# PM12_CONN.net
KiCad netlist of a schematic drawn in Altium Designer
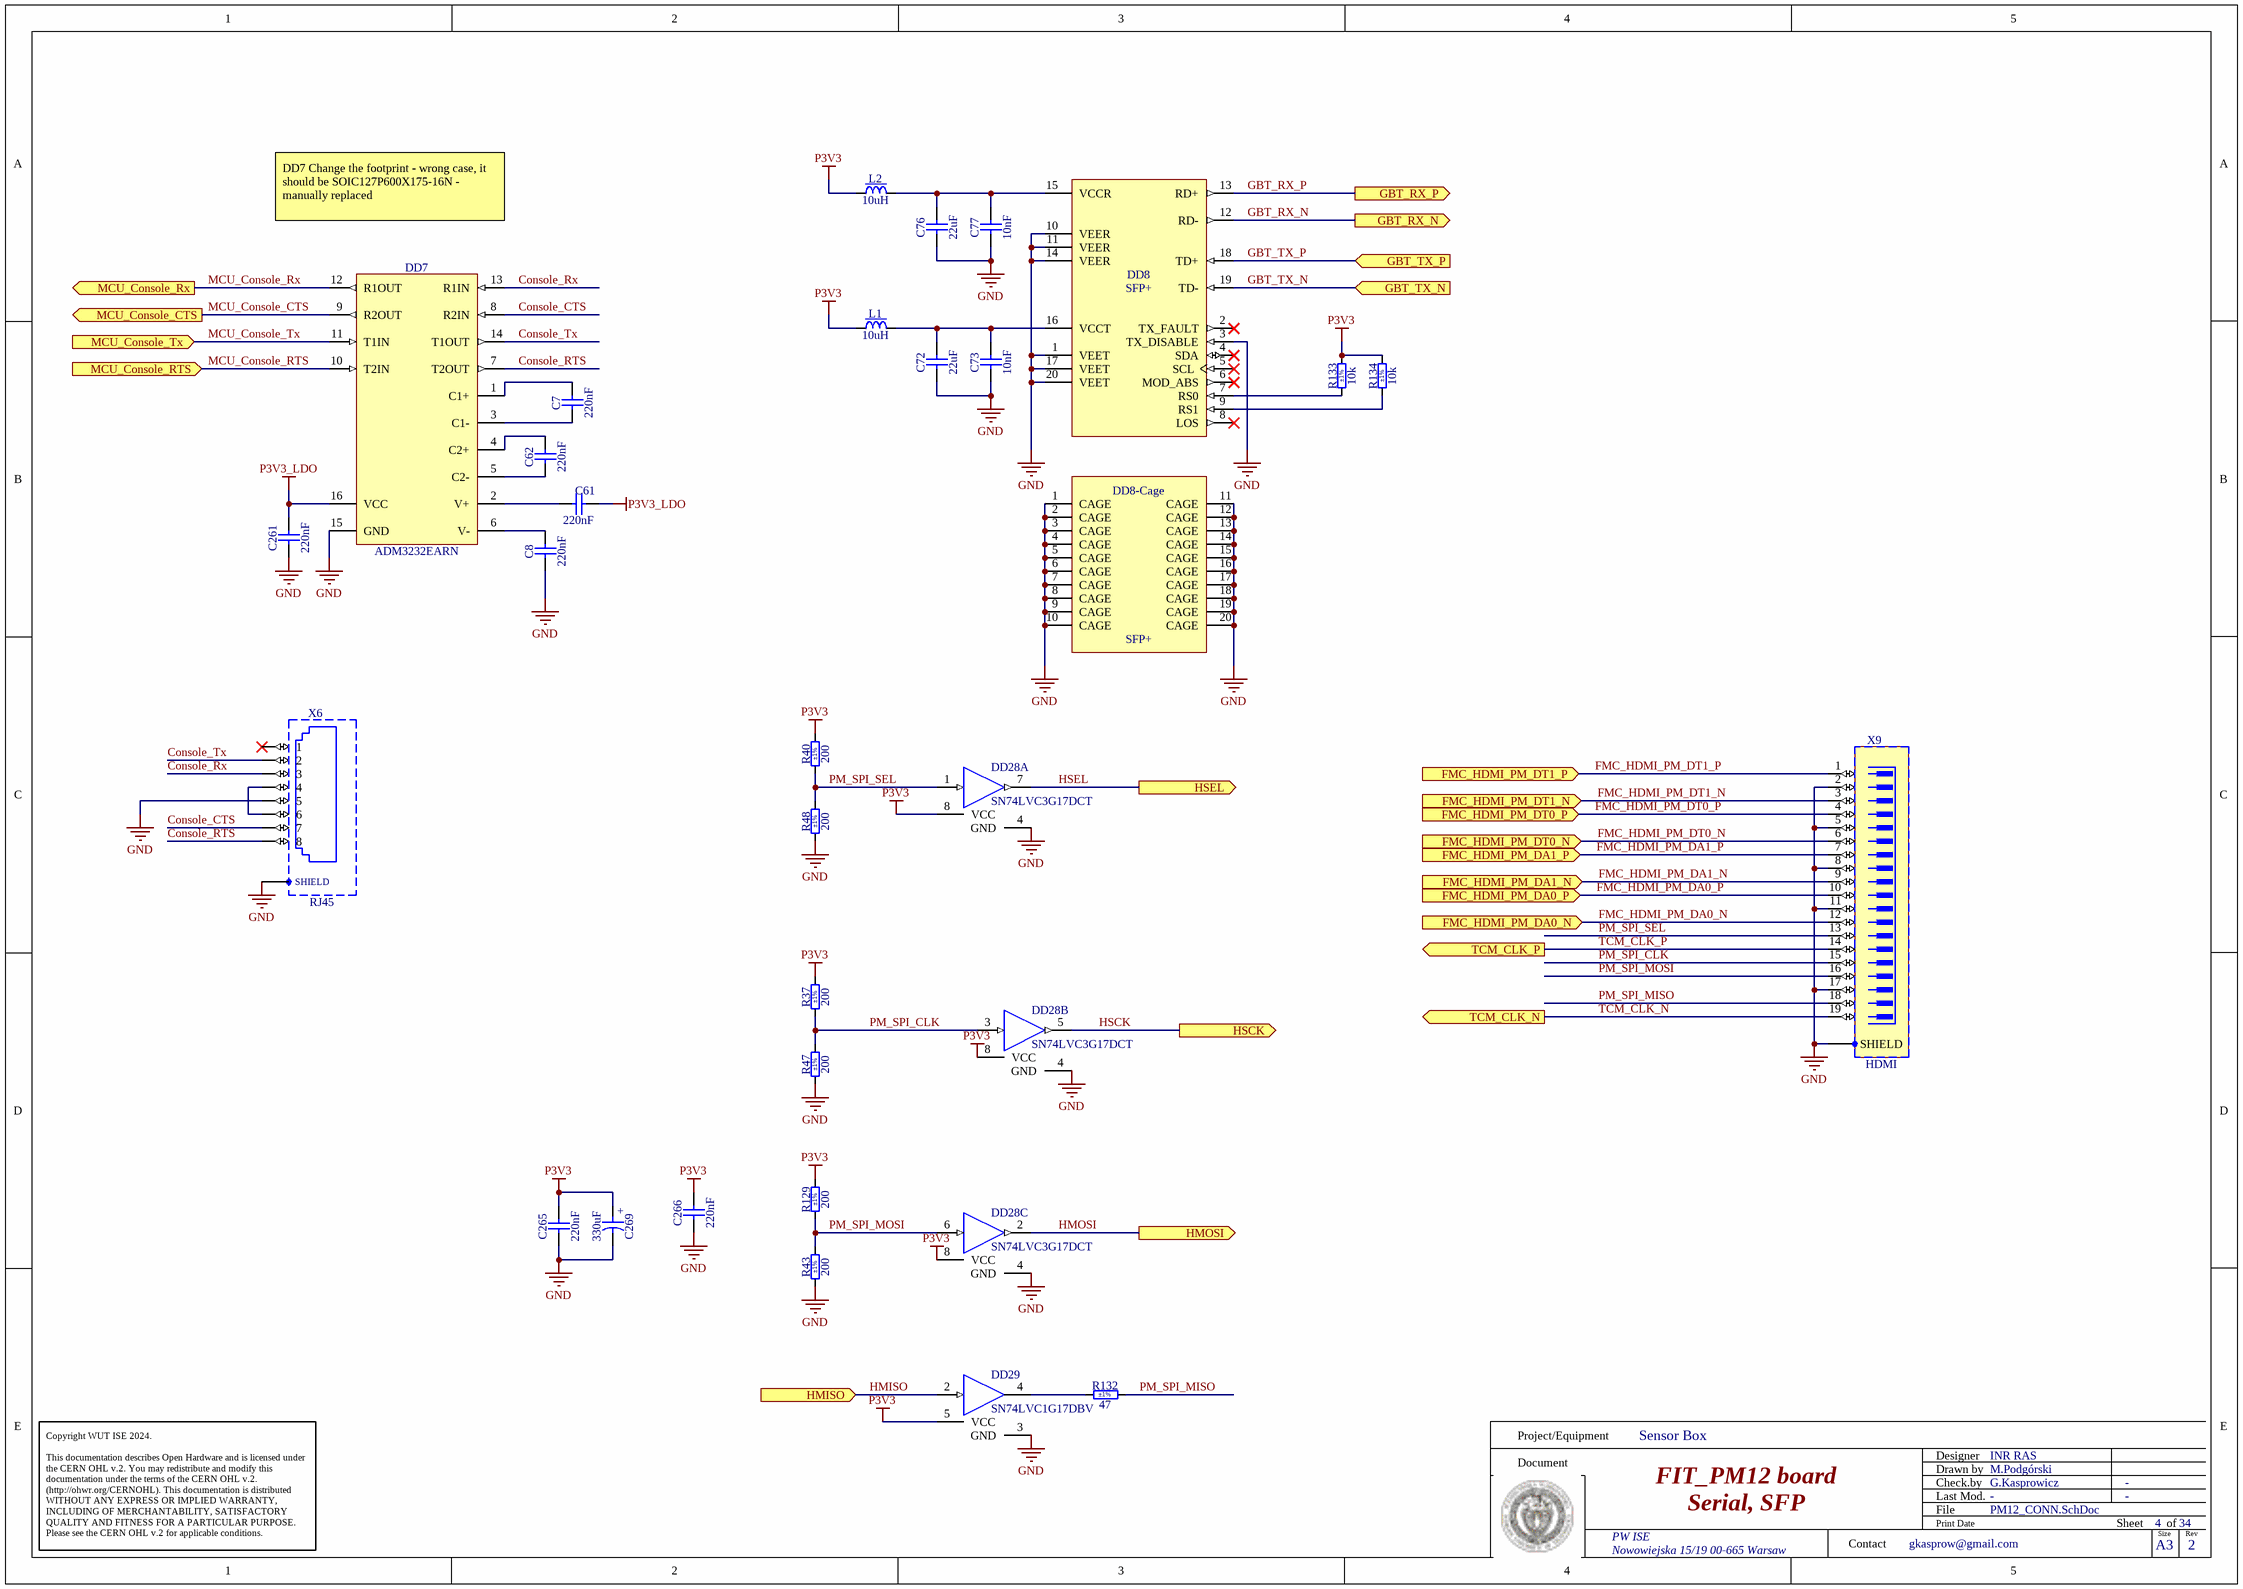
[diagram p0: PM12_CONN.SchDoc]

(export (version "E")
  (design (tool "Eeschema 10.0.6"))
  (components
    (comp (ref "C7")
      (value "220nF")
      (footprint "CAPC2012X135N")
      (description "Non-polarised capacitor")
      (fields
        (field (name "PART NUMBER") "CC0805_220NF_50V_10%_X7R")
        (field (name "VOLTAGE") "50V")
        (field (name "AUTHOR") "CERN DEM JLC")
      )
      (libsource (lib "Capacitors") (part "Capacitor - non polarized"))
    )
    (comp (ref "C8")
      (value "220nF")
      (footprint "CAPC2012X135N")
      (description "Non-polarised capacitor")
      (fields
        (field (name "PART NUMBER") "CC0805_220NF_50V_10%_X7R")
        (field (name "VOLTAGE") "50V")
        (field (name "AUTHOR") "CERN DEM JLC")
      )
      (libsource (lib "Capacitors") (part "Capacitor - non polarized"))
    )
    (comp (ref "C61")
      (value "220nF")
      (footprint "CAPC2012X135N")
      (description "Non-polarised capacitor")
      (fields
        (field (name "PART NUMBER") "CC0805_220NF_50V_10%_X7R")
        (field (name "VOLTAGE") "50V")
        (field (name "AUTHOR") "CERN DEM JLC")
      )
      (libsource (lib "Capacitors") (part "Capacitor - non polarized"))
    )
    (comp (ref "C62")
      (value "220nF")
      (footprint "CAPC2012X135N")
      (description "Non-polarised capacitor")
      (fields
        (field (name "PART NUMBER") "CC0805_220NF_50V_10%_X7R")
        (field (name "VOLTAGE") "50V")
        (field (name "AUTHOR") "CERN DEM JLC")
      )
      (libsource (lib "Capacitors") (part "Capacitor - non polarized"))
    )
    (comp (ref "C72")
      (value "22uF")
      (footprint "CAPC3216X180N")
      (description "Non-polarised capacitor")
      (fields
        (field (name "PART NUMBER") "CC1206_22UF_25V_20%_X5R")
        (field (name "VOLTAGE") "25V")
        (field (name "AUTHOR") "CERN DEM WB")
      )
      (libsource (lib "Capacitors") (part "Capacitor - non polarized"))
    )
    (comp (ref "C73")
      (value "10nF")
      (footprint "CAPC2012X135N")
      (description "Non-polarised capacitor")
      (fields
        (field (name "PART NUMBER") "CC0805_10NF_50V_10%_X7R")
        (field (name "VOLTAGE") "50V")
        (field (name "AUTHOR") "CERN DEM JLC")
      )
      (libsource (lib "Capacitors") (part "Capacitor - non polarized"))
    )
    (comp (ref "C76")
      (value "22uF")
      (footprint "CAPC3216X180N")
      (description "Non-polarised capacitor")
      (fields
        (field (name "PART NUMBER") "CC1206_22UF_25V_20%_X5R")
        (field (name "VOLTAGE") "25V")
        (field (name "AUTHOR") "CERN DEM WB")
      )
      (libsource (lib "Capacitors") (part "Capacitor - non polarized"))
    )
    (comp (ref "C77")
      (value "10nF")
      (footprint "CAPC2012X135N")
      (description "Non-polarised capacitor")
      (fields
        (field (name "PART NUMBER") "CC0805_10NF_50V_10%_X7R")
        (field (name "VOLTAGE") "50V")
        (field (name "AUTHOR") "CERN DEM JLC")
      )
      (libsource (lib "Capacitors") (part "Capacitor - non polarized"))
    )
    (comp (ref "C261")
      (value "220nF")
      (footprint "CAPC2012X135N")
      (description "Non-polarised capacitor")
      (fields
        (field (name "PART NUMBER") "CC0805_220NF_50V_10%_X7R")
        (field (name "VOLTAGE") "50V")
        (field (name "AUTHOR") "CERN DEM JLC")
      )
      (libsource (lib "Capacitors") (part "Capacitor - non polarized"))
    )
    (comp (ref "C265")
      (value "220nF")
      (footprint "CAPC2012X135N")
      (description "Non-polarised capacitor")
      (fields
        (field (name "PART NUMBER") "CC0805_220NF_50V_10%_X7R")
        (field (name "VOLTAGE") "50V")
        (field (name "AUTHOR") "CERN DEM JLC")
      )
      (libsource (lib "Capacitors") (part "Capacitor - non polarized"))
    )
    (comp (ref "C266")
      (value "220nF")
      (footprint "CAPC2012X135N")
      (description "Non-polarised capacitor")
      (fields
        (field (name "PART NUMBER") "CC0805_220NF_50V_10%_X7R")
        (field (name "VOLTAGE") "50V")
        (field (name "AUTHOR") "CERN DEM JLC")
      )
      (libsource (lib "Capacitors") (part "Capacitor - non polarized"))
    )
    (comp (ref "C269")
      (value "330uF")
      (footprint "CAPMP7343X310N")
      (description "Polarised capacitor")
      (fields
        (field (name "PART NUMBER") "CTE7343-31_330UF_6.3V_20%_LESR0015_KEMET_T520")
        (field (name "VOLTAGE") "6.3V")
        (field (name "AUTHOR") "CERN DEM JLC")
      )
      (libsource (lib "Capacitors") (part "Capacitor - polarized"))
    )
    (comp (ref "DD7")
      (value "ADM3232EARN")
      (footprint "SOIC127P600X175-16N")
      (description "±15 kV ESD Protected, 3.3 V, RS-232 Line Driver/Receiver")
      (fields (field (name "MANUFACTURER") "ANALOG DEVICES") (field (name "AUTHOR") "CERN DEM HF"))
      (libsource (lib "ICs And Semiconductors") (part "ADM3232EARN"))
    )
    (comp (ref "DD8")
      (value "SFP+")
      (footprint "AMPHENOL_UE76A203000")
      (description "20 Position SFP+ Connector (Small Form-factor Pluggable)")
      (fields
        (field (name "PART NUMBER") "AMPHENOL_UE76A203000")
        (field (name "MANUFACTURER") "AMPHENOL")
        (field (name "AUTHOR") "CERN DEM BC")
      )
      (libsource (lib "Connectors") (part "SFP+x1"))
    )
    (comp (ref "DD8-Cage")
      (value "SFP+")
      (footprint "AMPHENOL_U77A16131001")
      (description "SFP+ 1x1 Cage (20Pins)")
      (fields
        (field (name "PART NUMBER") "AMPHENOL_U77A16131001")
        (field (name "MANUFACTURER") "AMPHENOL")
        (field (name "AUTHOR") "CERN DEM BC")
      )
      (libsource (lib "Connectors") (part "SFP+ 1x1 Cage (20Pins)"))
    )
    (comp (ref "DD28")
      (value "SN74LVC3G17DCT")
      (footprint "SOP65P400X130-8N")
      (description "Triple Schmitt-Trigger Buffer")
      (fields (field (name "MANUFACTURER") "TEXAS INSTRUMENTS") (field (name "AUTHOR") "CERN DEM HF"))
      (libsource (lib "ICs And Semiconductors") (part "743G17"))
    )
    (comp (ref "DD29")
      (value "SN74LVC1G17DBV")
      (footprint "SOT95P280X145-5N")
      (description "Single Schmitt-Trigger Buffer")
      (fields
        (field (name "PART NUMBER") "SN74LVC1G17DBVR")
        (field (name "MANUFACTURER") "TEXAS INSTRUMENTS")
        (field (name "AUTHOR") "CERN DEM JLC")
      )
      (libsource (lib "ICs And Semiconductors") (part "741G17"))
    )
    (comp (ref "L1")
      (value "10uH")
      (footprint "INDM5552X200N")
      (description "Inductor With Core")
      (fields
        (field (name "PART NUMBER") "IND2020_10UH_20%_VISHAY_IHLP-2020BZ-11")
        (field (name "POWER") "2.2A")
        (field (name "AUTHOR") "CERN DEM HF")
      )
      (libsource (lib "Inductors & Transformers") (part "Inductor With Magnetic core"))
    )
    (comp (ref "L2")
      (value "10uH")
      (footprint "INDM5552X200N")
      (description "Inductor With Core")
      (fields
        (field (name "PART NUMBER") "IND2020_10UH_20%_VISHAY_IHLP-2020BZ-11")
        (field (name "POWER") "2.2A")
        (field (name "AUTHOR") "CERN DEM HF")
      )
      (libsource (lib "Inductors & Transformers") (part "Inductor With Magnetic core"))
    )
    (comp (ref "R37")
      (value "200")
      (footprint "RESC2012X60N")
      (description "Resistor - 1%")
      (fields
        (field (name "TOLERANCE") "±1%")
        (field (name "PART NUMBER") "R0805_200R_1%_0.125W_100PPM")
        (field (name "POWER") "0.125W")
        (field (name "AUTHOR") "CERN DEM JLC")
      )
      (libsource (lib "Resistors") (part "Resistor - 1%"))
    )
    (comp (ref "R40")
      (value "200")
      (footprint "RESC2012X60N")
      (description "Resistor - 1%")
      (fields
        (field (name "TOLERANCE") "±1%")
        (field (name "PART NUMBER") "R0805_200R_1%_0.125W_100PPM")
        (field (name "POWER") "0.125W")
        (field (name "AUTHOR") "CERN DEM JLC")
      )
      (libsource (lib "Resistors") (part "Resistor - 1%"))
    )
    (comp (ref "R43")
      (value "200")
      (footprint "RESC2012X60N")
      (description "Resistor - 1%")
      (fields
        (field (name "TOLERANCE") "±1%")
        (field (name "PART NUMBER") "R0805_200R_1%_0.125W_100PPM")
        (field (name "POWER") "0.125W")
        (field (name "AUTHOR") "CERN DEM JLC")
      )
      (libsource (lib "Resistors") (part "Resistor - 1%"))
    )
    (comp (ref "R47")
      (value "200")
      (footprint "RESC2012X60N")
      (description "Resistor - 1%")
      (fields
        (field (name "TOLERANCE") "±1%")
        (field (name "PART NUMBER") "R0805_200R_1%_0.125W_100PPM")
        (field (name "POWER") "0.125W")
        (field (name "AUTHOR") "CERN DEM JLC")
      )
      (libsource (lib "Resistors") (part "Resistor - 1%"))
    )
    (comp (ref "R48")
      (value "200")
      (footprint "RESC2012X60N")
      (description "Resistor - 1%")
      (fields
        (field (name "TOLERANCE") "±1%")
        (field (name "PART NUMBER") "R0805_200R_1%_0.125W_100PPM")
        (field (name "POWER") "0.125W")
        (field (name "AUTHOR") "CERN DEM JLC")
      )
      (libsource (lib "Resistors") (part "Resistor - 1%"))
    )
    (comp (ref "R129")
      (value "200")
      (footprint "RESC2012X60N")
      (description "Resistor - 1%")
      (fields
        (field (name "TOLERANCE") "±1%")
        (field (name "PART NUMBER") "R0805_200R_1%_0.125W_100PPM")
        (field (name "POWER") "0.125W")
        (field (name "AUTHOR") "CERN DEM JLC")
      )
      (libsource (lib "Resistors") (part "Resistor - 1%"))
    )
    (comp (ref "R132")
      (value "47")
      (footprint "RESC2012X60N")
      (description "Resistor - 1%")
      (fields
        (field (name "TOLERANCE") "±1%")
        (field (name "PART NUMBER") "R0805_47R_1%_0.125W_100PPM")
        (field (name "POWER") "0.125W")
        (field (name "AUTHOR") "CERN DEM JLC")
      )
      (libsource (lib "Resistors") (part "Resistor - 1%"))
    )
    (comp (ref "R133")
      (value "10k")
      (footprint "RESC2012X60N")
      (description "Resistor - 1%")
      (fields
        (field (name "TOLERANCE") "±1%")
        (field (name "PART NUMBER") "R0805_10K_1%_0.125W_100PPM")
        (field (name "POWER") "0.125W")
        (field (name "AUTHOR") "CERN DEM JLC")
      )
      (libsource (lib "Resistors") (part "Resistor - 1%"))
    )
    (comp (ref "R134")
      (value "10k")
      (footprint "RESC2012X60N")
      (description "Resistor - 1%")
      (fields
        (field (name "TOLERANCE") "±1%")
        (field (name "PART NUMBER") "R0805_10K_1%_0.125W_100PPM")
        (field (name "POWER") "0.125W")
        (field (name "AUTHOR") "CERN DEM JLC")
      )
      (libsource (lib "Resistors") (part "Resistor - 1%"))
    )
    (comp (ref "X6")
      (value "RJ45")
      (footprint "AMPHENOL_RJLSE4238101")
      (description "Connector RJ45 + Shield")
      (fields
        (field (name "PART NUMBER") "AMPHENOL_RJLSE4238101")
        (field (name "MANUFACTURER") "AMPHENOL")
        (field (name "AUTHOR") "CERN DEM HF")
      )
      (libsource (lib "Connectors") (part "Connector RJ45 + Shield"))
    )
    (comp (ref "X9")
      (value "HDMI")
      (footprint "MOLEX_47151-0001")
      (description "Connector HDMI 19 Male + 1 Shield")
      (fields
        (field (name "PART NUMBER") "MOLEX_47151-0001")
        (field (name "MANUFACTURER") "MOLEX")
        (field (name "AUTHOR") "CERN DEM JLC")
      )
      (libsource (lib "Connectors") (part "Connector HDMI 19 Male + 1 Shield"))
    )
  )
  (nets
    (net (code "1") (name "/Console_CTS") (class "Default")
      (node (ref "DD7") (pin "8") (pinfunction "R2IN_8") (pintype "input"))
      (node (ref "X6") (pin "7") (pinfunction "7_7") (pintype "bidirectional"))
    )
    (net (code "2") (name "/Console_RTS") (class "Default")
      (node (ref "DD7") (pin "7") (pinfunction "T2OUT_7") (pintype "output"))
      (node (ref "X6") (pin "8") (pinfunction "8_8") (pintype "bidirectional"))
    )
    (net (code "3") (name "/Console_Rx") (class "Default")
      (node (ref "DD7") (pin "13") (pinfunction "R1IN_13") (pintype "input"))
      (node (ref "X6") (pin "3") (pinfunction "3_3") (pintype "bidirectional"))
    )
    (net (code "4") (name "/Console_Tx") (class "Default")
      (node (ref "DD7") (pin "14") (pinfunction "T1OUT_14") (pintype "output"))
      (node (ref "X6") (pin "2") (pinfunction "2_2") (pintype "bidirectional"))
    )
    (net (code "5") (name "/FMC_HDMI_PM_DA0_N") (class "Default")
      (node (ref "X9") (pin "12") (pinfunction "12_12") (pintype "bidirectional"))
    )
    (net (code "6") (name "/FMC_HDMI_PM_DA0_P") (class "Default")
      (node (ref "X9") (pin "10") (pinfunction "10_10") (pintype "bidirectional"))
    )
    (net (code "7") (name "/FMC_HDMI_PM_DA1_N") (class "Default")
      (node (ref "X9") (pin "9") (pinfunction "9_9") (pintype "bidirectional"))
    )
    (net (code "8") (name "/FMC_HDMI_PM_DA1_P") (class "Default")
      (node (ref "X9") (pin "7") (pinfunction "7_7") (pintype "bidirectional"))
    )
    (net (code "9") (name "/FMC_HDMI_PM_DT0_N") (class "Default")
      (node (ref "X9") (pin "6") (pinfunction "6_6") (pintype "bidirectional"))
    )
    (net (code "10") (name "/FMC_HDMI_PM_DT0_P") (class "Default")
      (node (ref "X9") (pin "4") (pinfunction "4_4") (pintype "bidirectional"))
    )
    (net (code "11") (name "/FMC_HDMI_PM_DT1_N") (class "Default")
      (node (ref "X9") (pin "3") (pinfunction "3_3") (pintype "bidirectional"))
    )
    (net (code "12") (name "/FMC_HDMI_PM_DT1_P") (class "Default")
      (node (ref "X9") (pin "1") (pinfunction "1_1") (pintype "bidirectional"))
    )
    (net (code "13") (name "/GBT_RX_N") (class "Default")
      (node (ref "DD8") (pin "12") (pinfunction "RD-_12") (pintype "output"))
    )
    (net (code "14") (name "/GBT_RX_P") (class "Default")
      (node (ref "DD8") (pin "13") (pinfunction "RD+_13") (pintype "output"))
    )
    (net (code "15") (name "/GBT_TX_N") (class "Default")
      (node (ref "DD8") (pin "19") (pinfunction "TD-_19") (pintype "input"))
    )
    (net (code "16") (name "/GBT_TX_P") (class "Default")
      (node (ref "DD8") (pin "18") (pinfunction "TD+_18") (pintype "input"))
    )
    (net (code "17") (name "/HMISO") (class "Default")
      (node (ref "DD29") (pin "2") (pinfunction "IN_2") (pintype "input"))
    )
    (net (code "18") (name "/HMOSI") (class "Default")
      (node (ref "DD28") (pin "2") (pinfunction "OUT_2") (pintype "output"))
    )
    (net (code "19") (name "/HSCK") (class "Default")
      (node (ref "DD28") (pin "5") (pinfunction "OUT_5") (pintype "output"))
    )
    (net (code "20") (name "/HSEL") (class "Default")
      (node (ref "DD28") (pin "7") (pinfunction "OUT_7") (pintype "output"))
    )
    (net (code "21") (name "/MCU_Console_CTS") (class "Default")
      (node (ref "DD7") (pin "9") (pinfunction "R2OUT_9") (pintype "output"))
    )
    (net (code "22") (name "/MCU_Console_RTS") (class "Default")
      (node (ref "DD7") (pin "10") (pinfunction "T2IN_10") (pintype "input"))
    )
    (net (code "23") (name "/MCU_Console_Rx") (class "Default")
      (node (ref "DD7") (pin "12") (pinfunction "R1OUT_12") (pintype "output"))
    )
    (net (code "24") (name "/MCU_Console_Tx") (class "Default")
      (node (ref "DD7") (pin "11") (pinfunction "T1IN_11") (pintype "input"))
    )
    (net (code "25") (name "/PM_SPI_CLK") (class "Default")
      (node (ref "DD28") (pin "3") (pinfunction "IN_3") (pintype "input"))
      (node (ref "R37") (pin "1") (pinfunction "1_1") (pintype "passive"))
      (node (ref "R47") (pin "2") (pinfunction "2_2") (pintype "passive"))
      (node (ref "X9") (pin "15") (pinfunction "15_15") (pintype "bidirectional"))
    )
    (net (code "26") (name "/PM_SPI_MISO") (class "Default")
      (node (ref "R132") (pin "2") (pinfunction "2_2") (pintype "passive"))
      (node (ref "X9") (pin "18") (pinfunction "18_18") (pintype "bidirectional"))
    )
    (net (code "27") (name "/PM_SPI_MOSI") (class "Default")
      (node (ref "DD28") (pin "6") (pinfunction "IN_6") (pintype "input"))
      (node (ref "R129") (pin "1") (pinfunction "1_1") (pintype "passive"))
      (node (ref "R43") (pin "2") (pinfunction "2_2") (pintype "passive"))
      (node (ref "X9") (pin "16") (pinfunction "16_16") (pintype "bidirectional"))
    )
    (net (code "28") (name "/PM_SPI_SEL") (class "Default")
      (node (ref "DD28") (pin "1") (pinfunction "IN_1") (pintype "input"))
      (node (ref "R40") (pin "1") (pinfunction "1_1") (pintype "passive"))
      (node (ref "R48") (pin "2") (pinfunction "2_2") (pintype "passive"))
      (node (ref "X9") (pin "13") (pinfunction "13_13") (pintype "bidirectional"))
    )
    (net (code "29") (name "/TCM_CLK_N") (class "Default")
      (node (ref "X9") (pin "19") (pinfunction "19_19") (pintype "bidirectional"))
    )
    (net (code "30") (name "/TCM_CLK_P") (class "Default")
      (node (ref "X9") (pin "14") (pinfunction "14_14") (pintype "bidirectional"))
    )
    (net (code "31") (name "GND") (class "Default")
      (node (ref "C261") (pin "1") (pinfunction "1_1") (pintype "passive"))
      (node (ref "C265") (pin "1") (pinfunction "1_1") (pintype "passive"))
      (node (ref "C266") (pin "1") (pinfunction "1_1") (pintype "passive"))
      (node (ref "C269") (pin "2") (pinfunction "2_2") (pintype "passive"))
      (node (ref "C72") (pin "1") (pinfunction "1_1") (pintype "passive"))
      (node (ref "C73") (pin "1") (pinfunction "1_1") (pintype "passive"))
      (node (ref "C76") (pin "1") (pinfunction "1_1") (pintype "passive"))
      (node (ref "C77") (pin "1") (pinfunction "1_1") (pintype "passive"))
      (node (ref "C8") (pin "1") (pinfunction "1_1") (pintype "passive"))
      (node (ref "DD28") (pin "4") (pinfunction "GND_4") (pintype "power_in"))
      (node (ref "DD29") (pin "3") (pinfunction "GND_3") (pintype "power_in"))
      (node (ref "DD7") (pin "15") (pinfunction "GND_15") (pintype "power_in"))
      (node (ref "DD8") (pin "1") (pinfunction "VEET_1") (pintype "power_in"))
      (node (ref "DD8") (pin "10") (pinfunction "VEER_10") (pintype "power_in"))
      (node (ref "DD8") (pin "11") (pinfunction "VEER_11") (pintype "power_in"))
      (node (ref "DD8") (pin "14") (pinfunction "VEER_14") (pintype "power_in"))
      (node (ref "DD8") (pin "17") (pinfunction "VEET_17") (pintype "power_in"))
      (node (ref "DD8") (pin "20") (pinfunction "VEET_20") (pintype "power_in"))
      (node (ref "DD8") (pin "3") (pinfunction "TX_DISABLE_3") (pintype "input"))
      (node (ref "DD8-Cage") (pin "1") (pinfunction "CAGE_1") (pintype "power_in"))
      (node (ref "DD8-Cage") (pin "10") (pinfunction "CAGE_10") (pintype "power_in"))
      (node (ref "DD8-Cage") (pin "11") (pinfunction "CAGE_11") (pintype "power_in"))
      (node (ref "DD8-Cage") (pin "12") (pinfunction "CAGE_12") (pintype "power_in"))
      (node (ref "DD8-Cage") (pin "13") (pinfunction "CAGE_13") (pintype "power_in"))
      (node (ref "DD8-Cage") (pin "14") (pinfunction "CAGE_14") (pintype "power_in"))
      (node (ref "DD8-Cage") (pin "15") (pinfunction "CAGE_15") (pintype "power_in"))
      (node (ref "DD8-Cage") (pin "16") (pinfunction "CAGE_16") (pintype "power_in"))
      (node (ref "DD8-Cage") (pin "17") (pinfunction "CAGE_17") (pintype "power_in"))
      (node (ref "DD8-Cage") (pin "18") (pinfunction "CAGE_18") (pintype "power_in"))
      (node (ref "DD8-Cage") (pin "19") (pinfunction "CAGE_19") (pintype "power_in"))
      (node (ref "DD8-Cage") (pin "2") (pinfunction "CAGE_2") (pintype "power_in"))
      (node (ref "DD8-Cage") (pin "20") (pinfunction "CAGE_20") (pintype "power_in"))
      (node (ref "DD8-Cage") (pin "3") (pinfunction "CAGE_3") (pintype "power_in"))
      (node (ref "DD8-Cage") (pin "4") (pinfunction "CAGE_4") (pintype "power_in"))
      (node (ref "DD8-Cage") (pin "5") (pinfunction "CAGE_5") (pintype "power_in"))
      (node (ref "DD8-Cage") (pin "6") (pinfunction "CAGE_6") (pintype "power_in"))
      (node (ref "DD8-Cage") (pin "7") (pinfunction "CAGE_7") (pintype "power_in"))
      (node (ref "DD8-Cage") (pin "8") (pinfunction "CAGE_8") (pintype "power_in"))
      (node (ref "DD8-Cage") (pin "9") (pinfunction "CAGE_9") (pintype "power_in"))
      (node (ref "R43") (pin "1") (pinfunction "1_1") (pintype "passive"))
      (node (ref "R47") (pin "1") (pinfunction "1_1") (pintype "passive"))
      (node (ref "R48") (pin "1") (pinfunction "1_1") (pintype "passive"))
      (node (ref "X6") (pin "5") (pinfunction "5_5") (pintype "bidirectional"))
      (node (ref "X6") (pin "SHIELD") (pinfunction "SHIELD_SHIELD") (pintype "passive"))
      (node (ref "X9") (pin "11") (pinfunction "11_11") (pintype "bidirectional"))
      (node (ref "X9") (pin "17") (pinfunction "17_17") (pintype "bidirectional"))
      (node (ref "X9") (pin "2") (pinfunction "2_2") (pintype "bidirectional"))
      (node (ref "X9") (pin "5") (pinfunction "5_5") (pintype "bidirectional"))
      (node (ref "X9") (pin "8") (pinfunction "8_8") (pintype "bidirectional"))
      (node (ref "X9") (pin "SHIELD") (pinfunction "SHIELD_SHIELD") (pintype "power_in"))
    )
    (net (code "32") (name "Net-(DD7-C1+)") (class "Default")
      (node (ref "C7") (pin "2") (pinfunction "2_2") (pintype "passive"))
      (node (ref "DD7") (pin "1") (pinfunction "C1+_1") (pintype "passive"))
    )
    (net (code "33") (name "Net-(DD7-C1-)") (class "Default")
      (node (ref "C7") (pin "1") (pinfunction "1_1") (pintype "passive"))
      (node (ref "DD7") (pin "3") (pinfunction "C1-_3") (pintype "passive"))
    )
    (net (code "34") (name "Net-(DD7-C2+)") (class "Default")
      (node (ref "C62") (pin "2") (pinfunction "2_2") (pintype "passive"))
      (node (ref "DD7") (pin "4") (pinfunction "C2+_4") (pintype "passive"))
    )
    (net (code "35") (name "Net-(DD7-C2-)") (class "Default")
      (node (ref "C62") (pin "1") (pinfunction "1_1") (pintype "passive"))
      (node (ref "DD7") (pin "5") (pinfunction "C2-_5") (pintype "passive"))
    )
    (net (code "36") (name "Net-(DD7-V+)") (class "Default")
      (node (ref "C61") (pin "1") (pinfunction "1_1") (pintype "passive"))
      (node (ref "DD7") (pin "2") (pinfunction "V+_2") (pintype "power_in"))
    )
    (net (code "37") (name "Net-(DD7-V-)") (class "Default")
      (node (ref "C8") (pin "2") (pinfunction "2_2") (pintype "passive"))
      (node (ref "DD7") (pin "6") (pinfunction "V-_6") (pintype "power_in"))
    )
    (net (code "38") (name "Net-(DD8-RS0)") (class "Default")
      (node (ref "DD8") (pin "7") (pinfunction "RS0_7") (pintype "input"))
      (node (ref "R133") (pin "1") (pinfunction "1_1") (pintype "passive"))
    )
    (net (code "39") (name "Net-(DD8-RS1)") (class "Default")
      (node (ref "DD8") (pin "9") (pinfunction "RS1_9") (pintype "input"))
      (node (ref "R134") (pin "1") (pinfunction "1_1") (pintype "passive"))
    )
    (net (code "40") (name "Net-(DD8-VCCR)") (class "Default")
      (node (ref "C76") (pin "2") (pinfunction "2_2") (pintype "passive"))
      (node (ref "C77") (pin "2") (pinfunction "2_2") (pintype "passive"))
      (node (ref "DD8") (pin "15") (pinfunction "VCCR_15") (pintype "power_in"))
      (node (ref "L2") (pin "2") (pinfunction "2_2") (pintype "passive"))
    )
    (net (code "41") (name "Net-(DD8-VCCT)") (class "Default")
      (node (ref "C72") (pin "2") (pinfunction "2_2") (pintype "passive"))
      (node (ref "C73") (pin "2") (pinfunction "2_2") (pintype "passive"))
      (node (ref "DD8") (pin "16") (pinfunction "VCCT_16") (pintype "power_in"))
      (node (ref "L1") (pin "2") (pinfunction "2_2") (pintype "passive"))
    )
    (net (code "42") (name "Net-(DD29-OUT)") (class "Default")
      (node (ref "DD29") (pin "4") (pinfunction "OUT_4") (pintype "open_collector"))
      (node (ref "R132") (pin "1") (pinfunction "1_1") (pintype "passive"))
    )
    (net (code "43") (name "Net-(X6-Pad4)") (class "Default")
      (node (ref "X6") (pin "4") (pinfunction "4_4") (pintype "bidirectional"))
      (node (ref "X6") (pin "6") (pinfunction "6_6") (pintype "bidirectional"))
    )
    (net (code "44") (name "P3V3") (class "Default")
      (node (ref "C265") (pin "2") (pinfunction "2_2") (pintype "passive"))
      (node (ref "C266") (pin "2") (pinfunction "2_2") (pintype "passive"))
      (node (ref "C269") (pin "1") (pinfunction "1_1") (pintype "passive"))
      (node (ref "DD28") (pin "8") (pinfunction "VCC_8") (pintype "power_in"))
      (node (ref "DD29") (pin "5") (pinfunction "VCC_5") (pintype "power_in"))
      (node (ref "L1") (pin "1") (pinfunction "1_1") (pintype "passive"))
      (node (ref "L2") (pin "1") (pinfunction "1_1") (pintype "passive"))
      (node (ref "R129") (pin "2") (pinfunction "2_2") (pintype "passive"))
      (node (ref "R133") (pin "2") (pinfunction "2_2") (pintype "passive"))
      (node (ref "R134") (pin "2") (pinfunction "2_2") (pintype "passive"))
      (node (ref "R37") (pin "2") (pinfunction "2_2") (pintype "passive"))
      (node (ref "R40") (pin "2") (pinfunction "2_2") (pintype "passive"))
    )
    (net (code "45") (name "P3V3_LDO") (class "Default")
      (node (ref "C261") (pin "2") (pinfunction "2_2") (pintype "passive"))
      (node (ref "C61") (pin "2") (pinfunction "2_2") (pintype "passive"))
      (node (ref "DD7") (pin "16") (pinfunction "VCC_16") (pintype "power_in"))
    )
    (net (code "46") (name "unconnected-(DD8-LOS-Pad8)") (class "Default")
      (node (ref "DD8") (pin "8") (pinfunction "LOS_8") (pintype "output+no_connect"))
    )
    (net (code "47") (name "unconnected-(DD8-MOD_ABS-Pad6)") (class "Default")
      (node (ref "DD8") (pin "6") (pinfunction "MOD_ABS_6") (pintype "output+no_connect"))
    )
    (net (code "48") (name "unconnected-(DD8-SCL-Pad5)") (class "Default")
      (node (ref "DD8") (pin "5") (pinfunction "SCL_5") (pintype "input+no_connect"))
    )
    (net (code "49") (name "unconnected-(DD8-SDA-Pad4)") (class "Default")
      (node (ref "DD8") (pin "4") (pinfunction "SDA_4") (pintype "bidirectional+no_connect"))
    )
    (net (code "50") (name "unconnected-(DD8-TX_FAULT-Pad2)") (class "Default")
      (node (ref "DD8") (pin "2") (pinfunction "TX_FAULT_2") (pintype "output+no_connect"))
    )
    (net (code "51") (name "unconnected-(X6-Pad1)") (class "Default")
      (node (ref "X6") (pin "1") (pinfunction "1_1") (pintype "bidirectional+no_connect"))
    )
  )
)
